# Sensor_Bar.net
KiCad netlist of a schematic drawn in EAGLE
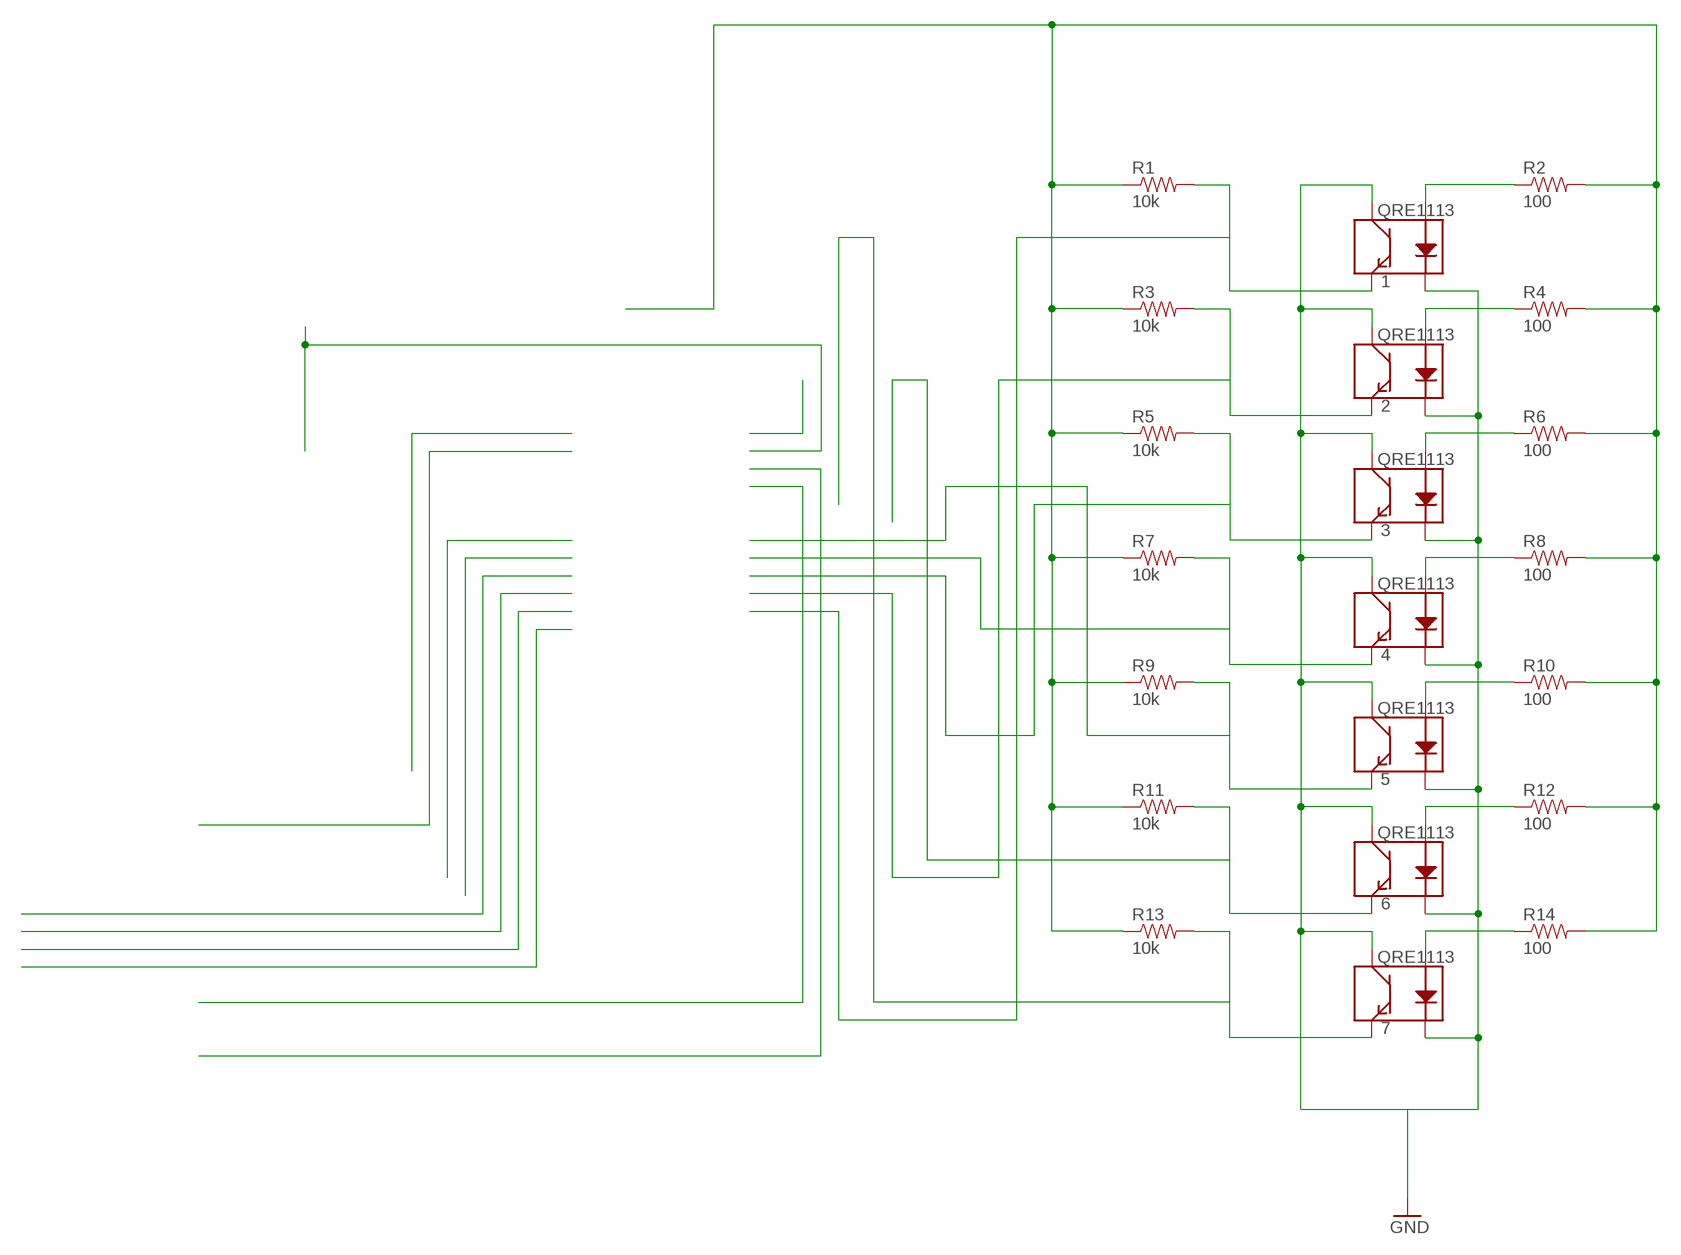
[diagram p0: schematic, sheet 1]

(export (version "E")
  (design (tool "Eeschema 10.0.6"))
  (components
    (comp (ref "1")
      (value "QRE1113")
      (footprint "eagle-import:QRE1113")
      (libsource (lib "eagle-import") (part "QRE1113"))
    )
    (comp (ref "2")
      (value "QRE1113")
      (footprint "eagle-import:QRE1113")
      (libsource (lib "eagle-import") (part "QRE1113"))
    )
    (comp (ref "3")
      (value "QRE1113")
      (footprint "eagle-import:QRE1113")
      (libsource (lib "eagle-import") (part "QRE1113"))
    )
    (comp (ref "4")
      (value "QRE1113")
      (footprint "eagle-import:QRE1113")
      (libsource (lib "eagle-import") (part "QRE1113"))
    )
    (comp (ref "5")
      (value "QRE1113")
      (footprint "eagle-import:QRE1113")
      (libsource (lib "eagle-import") (part "QRE1113"))
    )
    (comp (ref "6")
      (value "QRE1113")
      (footprint "eagle-import:QRE1113")
      (libsource (lib "eagle-import") (part "QRE1113"))
    )
    (comp (ref "7")
      (value "QRE1113")
      (footprint "eagle-import:QRE1113")
      (libsource (lib "eagle-import") (part "QRE1113"))
    )
    (comp (ref "R1")
      (value "10k")
      (footprint "eagle-import:0603-RES")
      (libsource (lib "eagle-import") (part "RESISTOR0603-RES"))
    )
    (comp (ref "R2")
      (value "100")
      (footprint "eagle-import:0805")
      (libsource (lib "eagle-import") (part "RESISTOR0805-RES"))
    )
    (comp (ref "R3")
      (value "10k")
      (footprint "eagle-import:0603-RES")
      (libsource (lib "eagle-import") (part "RESISTOR0603-RES"))
    )
    (comp (ref "R4")
      (value "100")
      (footprint "eagle-import:0805")
      (libsource (lib "eagle-import") (part "RESISTOR0805-RES"))
    )
    (comp (ref "R5")
      (value "10k")
      (footprint "eagle-import:0603-RES")
      (libsource (lib "eagle-import") (part "RESISTOR0603-RES"))
    )
    (comp (ref "R6")
      (value "100")
      (footprint "eagle-import:0805")
      (libsource (lib "eagle-import") (part "RESISTOR0805-RES"))
    )
    (comp (ref "R7")
      (value "10k")
      (footprint "eagle-import:0603-RES")
      (libsource (lib "eagle-import") (part "RESISTOR0603-RES"))
    )
    (comp (ref "R8")
      (value "100")
      (footprint "eagle-import:0805")
      (libsource (lib "eagle-import") (part "RESISTOR0805-RES"))
    )
    (comp (ref "R9")
      (value "10k")
      (footprint "eagle-import:0603-RES")
      (libsource (lib "eagle-import") (part "RESISTOR0603-RES"))
    )
    (comp (ref "R10")
      (value "100")
      (footprint "eagle-import:0805")
      (libsource (lib "eagle-import") (part "RESISTOR0805-RES"))
    )
    (comp (ref "R11")
      (value "10k")
      (footprint "eagle-import:0603-RES")
      (libsource (lib "eagle-import") (part "RESISTOR0603-RES"))
    )
    (comp (ref "R12")
      (value "100")
      (footprint "eagle-import:0805")
      (libsource (lib "eagle-import") (part "RESISTOR0805-RES"))
    )
    (comp (ref "R13")
      (value "10k")
      (footprint "eagle-import:0603-RES")
      (libsource (lib "eagle-import") (part "RESISTOR0603-RES"))
    )
    (comp (ref "R14")
      (value "100")
      (footprint "eagle-import:0805")
      (libsource (lib "eagle-import") (part "RESISTOR0805-RES"))
    )
  )
  (nets
    (net (code "1") (name "GND") (class "Default")
      (node (ref "1") (pin "2") (pinfunction "K_2") (pintype "bidirectional"))
      (node (ref "1") (pin "3") (pinfunction "C_3") (pintype "bidirectional"))
      (node (ref "2") (pin "2") (pinfunction "K_2") (pintype "bidirectional"))
      (node (ref "2") (pin "3") (pinfunction "C_3") (pintype "bidirectional"))
      (node (ref "3") (pin "2") (pinfunction "K_2") (pintype "bidirectional"))
      (node (ref "3") (pin "3") (pinfunction "C_3") (pintype "bidirectional"))
      (node (ref "4") (pin "2") (pinfunction "K_2") (pintype "bidirectional"))
      (node (ref "4") (pin "3") (pinfunction "C_3") (pintype "bidirectional"))
      (node (ref "5") (pin "2") (pinfunction "K_2") (pintype "bidirectional"))
      (node (ref "5") (pin "3") (pinfunction "C_3") (pintype "bidirectional"))
      (node (ref "6") (pin "2") (pinfunction "K_2") (pintype "bidirectional"))
      (node (ref "6") (pin "3") (pinfunction "C_3") (pintype "bidirectional"))
      (node (ref "7") (pin "2") (pinfunction "K_2") (pintype "bidirectional"))
      (node (ref "7") (pin "3") (pinfunction "C_3") (pintype "bidirectional"))
    )
    (net (code "2") (name "Net-(1-A)") (class "Default")
      (node (ref "1") (pin "1") (pinfunction "A_1") (pintype "bidirectional"))
      (node (ref "R2") (pin "1") (pinfunction "1_1") (pintype "passive"))
    )
    (net (code "3") (name "Net-(1-E)") (class "Default")
      (node (ref "1") (pin "4") (pinfunction "E_4") (pintype "bidirectional"))
      (node (ref "R1") (pin "2") (pinfunction "2_2") (pintype "passive"))
    )
    (net (code "4") (name "Net-(2-A)") (class "Default")
      (node (ref "2") (pin "1") (pinfunction "A_1") (pintype "bidirectional"))
      (node (ref "R4") (pin "1") (pinfunction "1_1") (pintype "passive"))
    )
    (net (code "5") (name "Net-(2-E)") (class "Default")
      (node (ref "2") (pin "4") (pinfunction "E_4") (pintype "bidirectional"))
      (node (ref "R3") (pin "2") (pinfunction "2_2") (pintype "passive"))
    )
    (net (code "6") (name "Net-(3-A)") (class "Default")
      (node (ref "3") (pin "1") (pinfunction "A_1") (pintype "bidirectional"))
      (node (ref "R6") (pin "1") (pinfunction "1_1") (pintype "passive"))
    )
    (net (code "7") (name "Net-(3-E)") (class "Default")
      (node (ref "3") (pin "4") (pinfunction "E_4") (pintype "bidirectional"))
      (node (ref "R5") (pin "2") (pinfunction "2_2") (pintype "passive"))
    )
    (net (code "8") (name "Net-(4-A)") (class "Default")
      (node (ref "4") (pin "1") (pinfunction "A_1") (pintype "bidirectional"))
      (node (ref "R8") (pin "1") (pinfunction "1_1") (pintype "passive"))
    )
    (net (code "9") (name "Net-(4-E)") (class "Default")
      (node (ref "4") (pin "4") (pinfunction "E_4") (pintype "bidirectional"))
      (node (ref "R7") (pin "2") (pinfunction "2_2") (pintype "passive"))
    )
    (net (code "10") (name "Net-(5-A)") (class "Default")
      (node (ref "5") (pin "1") (pinfunction "A_1") (pintype "bidirectional"))
      (node (ref "R10") (pin "1") (pinfunction "1_1") (pintype "passive"))
    )
    (net (code "11") (name "Net-(5-E)") (class "Default")
      (node (ref "5") (pin "4") (pinfunction "E_4") (pintype "bidirectional"))
      (node (ref "R9") (pin "2") (pinfunction "2_2") (pintype "passive"))
    )
    (net (code "12") (name "Net-(6-A)") (class "Default")
      (node (ref "6") (pin "1") (pinfunction "A_1") (pintype "bidirectional"))
      (node (ref "R12") (pin "1") (pinfunction "1_1") (pintype "passive"))
    )
    (net (code "13") (name "Net-(6-E)") (class "Default")
      (node (ref "6") (pin "4") (pinfunction "E_4") (pintype "bidirectional"))
      (node (ref "R11") (pin "2") (pinfunction "2_2") (pintype "passive"))
    )
    (net (code "14") (name "Net-(7-A)") (class "Default")
      (node (ref "7") (pin "1") (pinfunction "A_1") (pintype "bidirectional"))
      (node (ref "R14") (pin "1") (pinfunction "1_1") (pintype "passive"))
    )
    (net (code "15") (name "Net-(7-E)") (class "Default")
      (node (ref "7") (pin "4") (pinfunction "E_4") (pintype "bidirectional"))
      (node (ref "R13") (pin "2") (pinfunction "2_2") (pintype "passive"))
    )
    (net (code "16") (name "Net-(R1-Pad1)") (class "Default")
      (node (ref "R1") (pin "1") (pinfunction "1_1") (pintype "passive"))
      (node (ref "R10") (pin "2") (pinfunction "2_2") (pintype "passive"))
      (node (ref "R11") (pin "1") (pinfunction "1_1") (pintype "passive"))
      (node (ref "R12") (pin "2") (pinfunction "2_2") (pintype "passive"))
      (node (ref "R13") (pin "1") (pinfunction "1_1") (pintype "passive"))
      (node (ref "R14") (pin "2") (pinfunction "2_2") (pintype "passive"))
      (node (ref "R2") (pin "2") (pinfunction "2_2") (pintype "passive"))
      (node (ref "R3") (pin "1") (pinfunction "1_1") (pintype "passive"))
      (node (ref "R4") (pin "2") (pinfunction "2_2") (pintype "passive"))
      (node (ref "R5") (pin "1") (pinfunction "1_1") (pintype "passive"))
      (node (ref "R6") (pin "2") (pinfunction "2_2") (pintype "passive"))
      (node (ref "R7") (pin "1") (pinfunction "1_1") (pintype "passive"))
      (node (ref "R8") (pin "2") (pinfunction "2_2") (pintype "passive"))
      (node (ref "R9") (pin "1") (pinfunction "1_1") (pintype "passive"))
    )
  )
)
